# nRF51_key.net
KiCad netlist of a schematic drawn in EAGLE
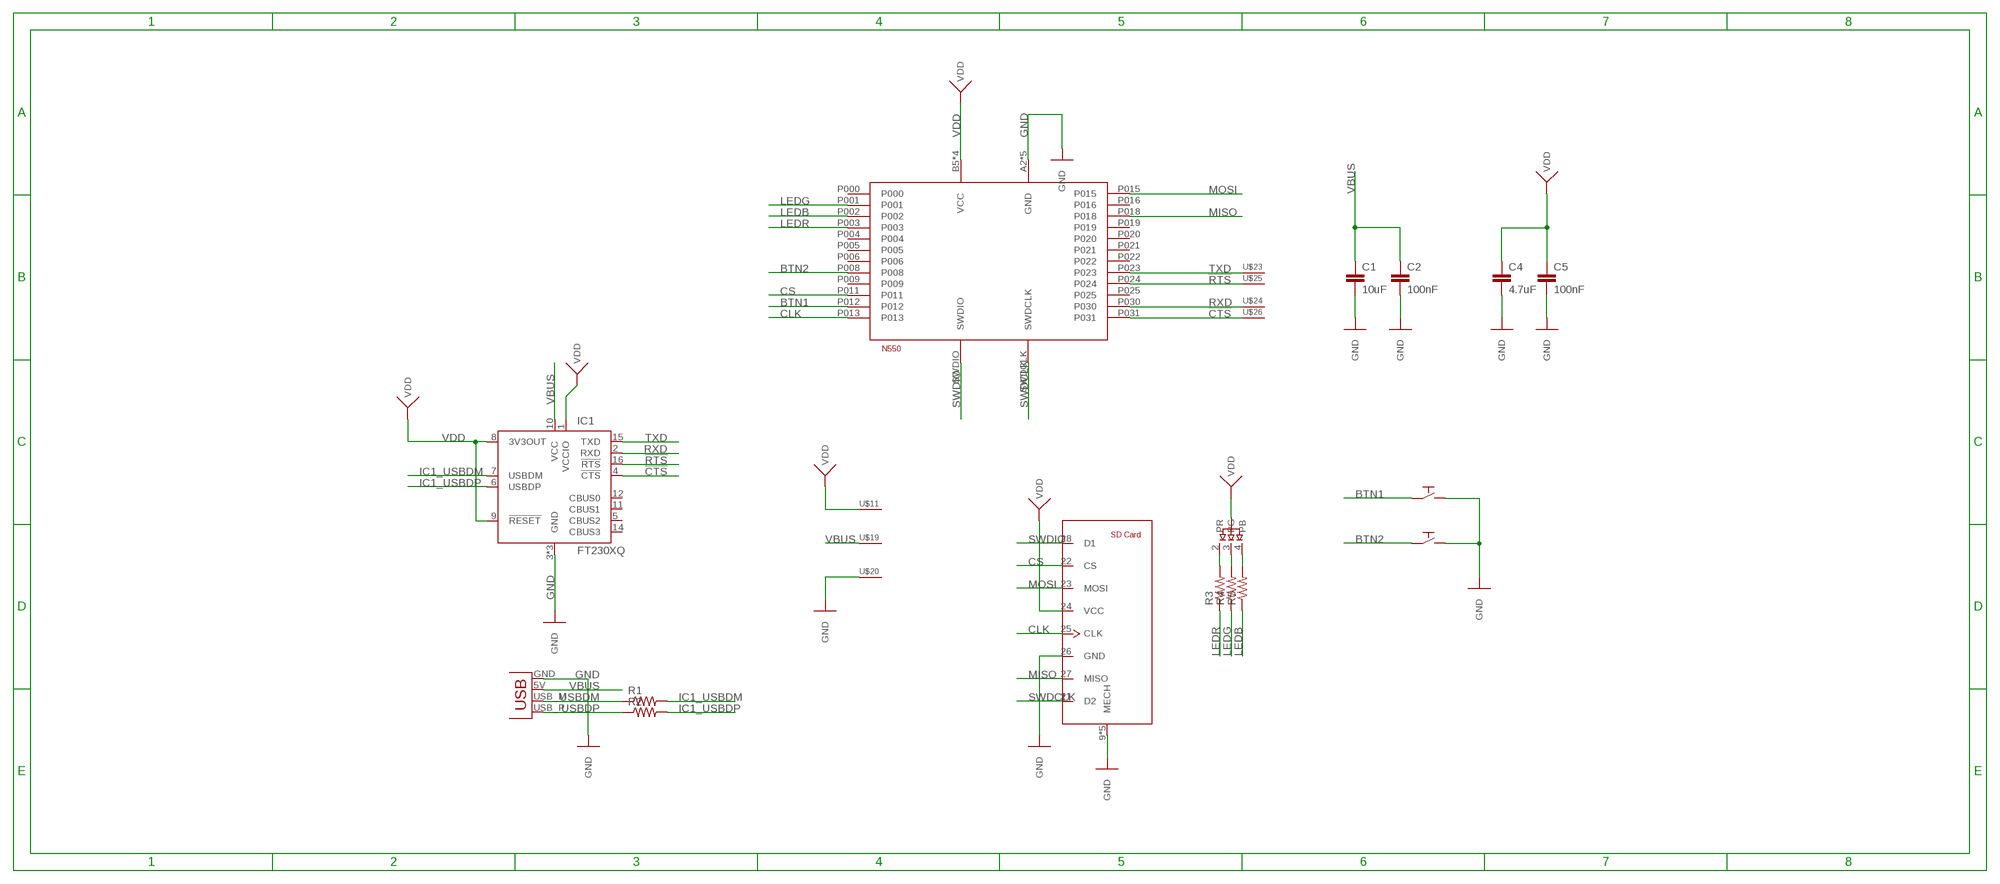
[diagram p0: schematic, sheet 1]

(export (version "E")
  (design (tool "Eeschema 10.0.6"))
  (components
    (comp (ref "C1")
      (value "10uF")
      (footprint "eagle-import:C0603")
      (libsource (lib "eagle-import") (part "CAPACITOR0603"))
    )
    (comp (ref "C2")
      (value "100nF")
      (footprint "eagle-import:C0603")
      (libsource (lib "eagle-import") (part "CAPACITOR0603"))
    )
    (comp (ref "C4")
      (value "4.7uF")
      (footprint "eagle-import:C0603")
      (libsource (lib "eagle-import") (part "CAPACITOR0603"))
    )
    (comp (ref "C5")
      (value "100nF")
      (footprint "eagle-import:C0603")
      (libsource (lib "eagle-import") (part "CAPACITOR0603"))
    )
    (comp (ref "D1")
      (value "LRTBR48G")
      (footprint "eagle-import:LRTBR48GP9Q71R7S526NP68")
      (libsource (lib "eagle-import") (part "LRTBR48G"))
    )
    (comp (ref "IC1")
      (value "FT230XQ")
      (footprint "eagle-import:QFN16")
      (fields (field (name "MF") "FTDI"))
      (libsource (lib "eagle-import") (part "FT230XQ"))
    )
    (comp (ref "J1")
      (value "47571-0001")
      (footprint "eagle-import:47571-0001")
      (libsource (lib "eagle-import") (part "47571-0001"))
    )
    (comp (ref "R1")
      (value "RESISTOR0603")
      (footprint "eagle-import:R0603")
      (libsource (lib "eagle-import") (part "RESISTOR0603"))
    )
    (comp (ref "R2")
      (value "RESISTOR0603")
      (footprint "eagle-import:R0603")
      (libsource (lib "eagle-import") (part "RESISTOR0603"))
    )
    (comp (ref "R3")
      (value "RESISTOR0603")
      (footprint "eagle-import:R0603")
      (libsource (lib "eagle-import") (part "RESISTOR0603"))
    )
    (comp (ref "R4")
      (value "RESISTOR0603")
      (footprint "eagle-import:R0603")
      (libsource (lib "eagle-import") (part "RESISTOR0603"))
    )
    (comp (ref "R5")
      (value "RESISTOR0603")
      (footprint "eagle-import:R0603")
      (libsource (lib "eagle-import") (part "RESISTOR0603"))
    )
    (comp (ref "SPST1")
      (value "PTS526SK08")
      (footprint "eagle-import:PTS526SKG15SMTR2LFS")
      (libsource (lib "eagle-import") (part "PTS526SK08"))
    )
    (comp (ref "SPST2")
      (value "PTS526SK08")
      (footprint "eagle-import:PTS526SKG15SMTR2LFS")
      (libsource (lib "eagle-import") (part "PTS526SK08"))
    )
    (comp (ref "U$1")
      (value "N550")
      (footprint "eagle-import:N550")
      (libsource (lib "eagle-import") (part "N550"))
    )
    (comp (ref "U$11")
      (value "PAD")
      (footprint "eagle-import:PAD_0.8")
      (libsource (lib "eagle-import") (part "PAD"))
    )
    (comp (ref "U$19")
      (value "PAD")
      (footprint "eagle-import:PAD_0.8")
      (libsource (lib "eagle-import") (part "PAD"))
    )
    (comp (ref "U$20")
      (value "PAD")
      (footprint "eagle-import:PAD_0.8")
      (libsource (lib "eagle-import") (part "PAD"))
    )
    (comp (ref "U$23")
      (value "PAD")
      (footprint "eagle-import:PAD_0.8")
      (libsource (lib "eagle-import") (part "PAD"))
    )
    (comp (ref "U$24")
      (value "PAD")
      (footprint "eagle-import:PAD_0.8")
      (libsource (lib "eagle-import") (part "PAD"))
    )
    (comp (ref "U$25")
      (value "PAD")
      (footprint "eagle-import:PAD_0.8")
      (libsource (lib "eagle-import") (part "PAD"))
    )
    (comp (ref "U$26")
      (value "PAD")
      (footprint "eagle-import:PAD_0.8")
      (libsource (lib "eagle-import") (part "PAD"))
    )
    (comp (ref "X1")
      (value "USBPCB")
      (footprint "eagle-import:USB-A-PCB")
      (libsource (lib "eagle-import") (part "USBPCB"))
    )
  )
  (nets
    (net (code "1") (name "/BTN1") (class "Default")
      (node (ref "SPST1") (pin "1") (pinfunction "P$1_1") (pintype "passive"))
      (node (ref "SPST1") (pin "2") (pinfunction "P$1_2") (pintype "passive"))
      (node (ref "U$1") (pin "P012") (pinfunction "P012_P012") (pintype "bidirectional"))
    )
    (net (code "2") (name "/BTN2") (class "Default")
      (node (ref "SPST2") (pin "1") (pinfunction "P$1_1") (pintype "passive"))
      (node (ref "SPST2") (pin "2") (pinfunction "P$1_2") (pintype "passive"))
      (node (ref "U$1") (pin "P008") (pinfunction "P008_P008") (pintype "bidirectional"))
    )
    (net (code "3") (name "/CLK") (class "Default")
      (node (ref "J1") (pin "25") (pinfunction "CLK_25") (pintype "input"))
      (node (ref "U$1") (pin "P013") (pinfunction "P013_P013") (pintype "bidirectional"))
    )
    (net (code "4") (name "/CS") (class "Default")
      (node (ref "J1") (pin "22") (pinfunction "CS_22") (pintype "bidirectional"))
      (node (ref "U$1") (pin "P011") (pinfunction "P011_P011") (pintype "bidirectional"))
    )
    (net (code "5") (name "/IC1_USBDM") (class "Default")
      (node (ref "IC1") (pin "7") (pinfunction "USBDM_7") (pintype "input"))
      (node (ref "R1") (pin "2") (pinfunction "2_2") (pintype "passive"))
    )
    (net (code "6") (name "/IC1_USBDP") (class "Default")
      (node (ref "IC1") (pin "6") (pinfunction "USBDP_6") (pintype "input"))
      (node (ref "R2") (pin "2") (pinfunction "2_2") (pintype "passive"))
    )
    (net (code "7") (name "/LEDB") (class "Default")
      (node (ref "R5") (pin "1") (pinfunction "1_1") (pintype "passive"))
      (node (ref "U$1") (pin "P002") (pinfunction "P002_P002") (pintype "bidirectional"))
    )
    (net (code "8") (name "/LEDG") (class "Default")
      (node (ref "R4") (pin "1") (pinfunction "1_1") (pintype "passive"))
      (node (ref "U$1") (pin "P001") (pinfunction "P001_P001") (pintype "bidirectional"))
    )
    (net (code "9") (name "/LEDR") (class "Default")
      (node (ref "R3") (pin "1") (pinfunction "1_1") (pintype "passive"))
      (node (ref "U$1") (pin "P003") (pinfunction "P003_P003") (pintype "bidirectional"))
    )
    (net (code "10") (name "/MISO") (class "Default")
      (node (ref "J1") (pin "27") (pinfunction "MISO_27") (pintype "bidirectional"))
      (node (ref "U$1") (pin "P018") (pinfunction "P018_P018") (pintype "bidirectional"))
    )
    (net (code "11") (name "/MOSI") (class "Default")
      (node (ref "J1") (pin "23") (pinfunction "MOSI_23") (pintype "bidirectional"))
      (node (ref "U$1") (pin "P015") (pinfunction "P015_P015") (pintype "bidirectional"))
    )
    (net (code "12") (name "/RXD") (class "Default")
      (node (ref "IC1") (pin "2") (pinfunction "RXD_2") (pintype "input"))
      (node (ref "U$1") (pin "P030") (pinfunction "P030_P030") (pintype "bidirectional"))
      (node (ref "U$24") (pin "PAD") (pinfunction "P$1_PAD") (pintype "bidirectional"))
    )
    (net (code "13") (name "/SWDCLK") (class "Default")
      (node (ref "J1") (pin "21") (pinfunction "D2_21") (pintype "tri_state"))
      (node (ref "U$1") (pin "SWDCLK") (pinfunction "SWDCLK_SWDCLK") (pintype "bidirectional"))
    )
    (net (code "14") (name "/SWDIO") (class "Default")
      (node (ref "J1") (pin "28") (pinfunction "D1_28") (pintype "tri_state"))
      (node (ref "U$1") (pin "SWDIO") (pinfunction "SWDIO_SWDIO") (pintype "bidirectional"))
    )
    (net (code "15") (name "/TXD") (class "Default")
      (node (ref "IC1") (pin "15") (pinfunction "TXD_15") (pintype "output"))
      (node (ref "U$1") (pin "P023") (pinfunction "P023_P023") (pintype "bidirectional"))
      (node (ref "U$23") (pin "PAD") (pinfunction "P$1_PAD") (pintype "bidirectional"))
    )
    (net (code "16") (name "/USBDM") (class "Default")
      (node (ref "R1") (pin "1") (pinfunction "1_1") (pintype "passive"))
      (node (ref "X1") (pin "USB_M") (pinfunction "D-_USB_M") (pintype "bidirectional"))
    )
    (net (code "17") (name "/USBDP") (class "Default")
      (node (ref "R2") (pin "1") (pinfunction "1_1") (pintype "passive"))
      (node (ref "X1") (pin "USB_P") (pinfunction "D+_USB_P") (pintype "bidirectional"))
    )
    (net (code "18") (name "/VBUS") (class "Default")
      (node (ref "C1") (pin "1") (pinfunction "1_1") (pintype "passive"))
      (node (ref "C2") (pin "1") (pinfunction "1_1") (pintype "passive"))
      (node (ref "IC1") (pin "10") (pinfunction "VCC_10") (pintype "power_in"))
      (node (ref "U$19") (pin "PAD") (pinfunction "P$1_PAD") (pintype "bidirectional"))
      (node (ref "X1") (pin "5V") (pinfunction "VBUS_5V") (pintype "bidirectional"))
    )
    (net (code "19") (name "/~{CTS}") (class "Default")
      (node (ref "IC1") (pin "4") (pinfunction "~{CTS}_4") (pintype "input"))
      (node (ref "U$1") (pin "P031") (pinfunction "P031_P031") (pintype "bidirectional"))
      (node (ref "U$26") (pin "PAD") (pinfunction "P$1_PAD") (pintype "bidirectional"))
    )
    (net (code "20") (name "/~{RTS}") (class "Default")
      (node (ref "IC1") (pin "16") (pinfunction "~{RTS}_16") (pintype "output"))
      (node (ref "U$1") (pin "P024") (pinfunction "P024_P024") (pintype "bidirectional"))
      (node (ref "U$25") (pin "PAD") (pinfunction "P$1_PAD") (pintype "bidirectional"))
    )
    (net (code "21") (name "GND") (class "Default")
      (node (ref "C1") (pin "2") (pinfunction "2_2") (pintype "passive"))
      (node (ref "C2") (pin "2") (pinfunction "2_2") (pintype "passive"))
      (node (ref "C4") (pin "2") (pinfunction "2_2") (pintype "passive"))
      (node (ref "C5") (pin "2") (pinfunction "2_2") (pintype "passive"))
      (node (ref "IC1") (pin "13") (pinfunction "GND_13") (pintype "power_in"))
      (node (ref "IC1") (pin "3") (pinfunction "GND_3") (pintype "power_in"))
      (node (ref "IC1") (pin "EXP") (pinfunction "GND_EXP") (pintype "power_in"))
      (node (ref "J1") (pin "10") (pinfunction "MECH_10") (pintype "bidirectional"))
      (node (ref "J1") (pin "11") (pinfunction "MECH_11") (pintype "bidirectional"))
      (node (ref "J1") (pin "12") (pinfunction "MECH_12") (pintype "bidirectional"))
      (node (ref "J1") (pin "13") (pinfunction "MECH_13") (pintype "bidirectional"))
      (node (ref "J1") (pin "26") (pinfunction "GND_26") (pintype "power_in"))
      (node (ref "J1") (pin "9") (pinfunction "MECH_9") (pintype "bidirectional"))
      (node (ref "SPST1") (pin "3") (pinfunction "P$2_3") (pintype "passive"))
      (node (ref "SPST1") (pin "4") (pinfunction "P$2_4") (pintype "passive"))
      (node (ref "SPST2") (pin "3") (pinfunction "P$2_3") (pintype "passive"))
      (node (ref "SPST2") (pin "4") (pinfunction "P$2_4") (pintype "passive"))
      (node (ref "U$1") (pin "A2") (pinfunction "GND_A2") (pintype "bidirectional"))
      (node (ref "U$1") (pin "A3") (pinfunction "GND_A3") (pintype "bidirectional"))
      (node (ref "U$1") (pin "A4") (pinfunction "GND_A4") (pintype "bidirectional"))
      (node (ref "U$1") (pin "A5") (pinfunction "GND_A5") (pintype "bidirectional"))
      (node (ref "U$1") (pin "A6") (pinfunction "GND_A6") (pintype "bidirectional"))
      (node (ref "U$20") (pin "PAD") (pinfunction "P$1_PAD") (pintype "bidirectional"))
      (node (ref "X1") (pin "GND") (pinfunction "GND_GND") (pintype "bidirectional"))
    )
    (net (code "22") (name "Net-(D1-PB)") (class "Default")
      (node (ref "D1") (pin "4") (pinfunction "PB_4") (pintype "bidirectional"))
      (node (ref "R5") (pin "2") (pinfunction "2_2") (pintype "passive"))
    )
    (net (code "23") (name "Net-(D1-PG)") (class "Default")
      (node (ref "D1") (pin "3") (pinfunction "PG_3") (pintype "bidirectional"))
      (node (ref "R4") (pin "2") (pinfunction "2_2") (pintype "passive"))
    )
    (net (code "24") (name "Net-(D1-PR)") (class "Default")
      (node (ref "D1") (pin "2") (pinfunction "PR_2") (pintype "bidirectional"))
      (node (ref "R3") (pin "2") (pinfunction "2_2") (pintype "passive"))
    )
    (net (code "25") (name "VDD") (class "Default")
      (node (ref "C4") (pin "1") (pinfunction "1_1") (pintype "passive"))
      (node (ref "C5") (pin "1") (pinfunction "1_1") (pintype "passive"))
      (node (ref "D1") (pin "1") (pinfunction "P$1_1") (pintype "bidirectional"))
      (node (ref "IC1") (pin "1") (pinfunction "VCCIO_1") (pintype "power_in"))
      (node (ref "IC1") (pin "8") (pinfunction "3V3OUT_8") (pintype "passive"))
      (node (ref "IC1") (pin "9") (pinfunction "~{RESET}_9") (pintype "input"))
      (node (ref "J1") (pin "24") (pinfunction "VCC_24") (pintype "power_in"))
      (node (ref "U$1") (pin "B5") (pinfunction "VCC_B5") (pintype "bidirectional"))
      (node (ref "U$1") (pin "B6") (pinfunction "VCC_B6") (pintype "bidirectional"))
      (node (ref "U$1") (pin "C5") (pinfunction "VCC_C5") (pintype "bidirectional"))
      (node (ref "U$1") (pin "C6") (pinfunction "VCC_C6") (pintype "bidirectional"))
      (node (ref "U$11") (pin "PAD") (pinfunction "P$1_PAD") (pintype "bidirectional"))
    )
    (net (code "26") (name "unconnected-(IC1-CBUS0-Pad12)") (class "Default")
      (node (ref "IC1") (pin "12") (pinfunction "CBUS0_12") (pintype "bidirectional"))
    )
    (net (code "27") (name "unconnected-(IC1-CBUS1-Pad11)") (class "Default")
      (node (ref "IC1") (pin "11") (pinfunction "CBUS1_11") (pintype "bidirectional"))
    )
    (net (code "28") (name "unconnected-(IC1-CBUS2-Pad5)") (class "Default")
      (node (ref "IC1") (pin "5") (pinfunction "CBUS2_5") (pintype "bidirectional"))
    )
    (net (code "29") (name "unconnected-(IC1-CBUS3-Pad14)") (class "Default")
      (node (ref "IC1") (pin "14") (pinfunction "CBUS3_14") (pintype "bidirectional"))
    )
    (net (code "30") (name "unconnected-(U$1-PadP000)") (class "Default")
      (node (ref "U$1") (pin "P000") (pinfunction "P000_P000") (pintype "bidirectional"))
    )
    (net (code "31") (name "unconnected-(U$1-PadP004)") (class "Default")
      (node (ref "U$1") (pin "P004") (pinfunction "P004_P004") (pintype "bidirectional"))
    )
    (net (code "32") (name "unconnected-(U$1-PadP005)") (class "Default")
      (node (ref "U$1") (pin "P005") (pinfunction "P005_P005") (pintype "bidirectional"))
    )
    (net (code "33") (name "unconnected-(U$1-PadP006)") (class "Default")
      (node (ref "U$1") (pin "P006") (pinfunction "P006_P006") (pintype "bidirectional"))
    )
    (net (code "34") (name "unconnected-(U$1-PadP009)") (class "Default")
      (node (ref "U$1") (pin "P009") (pinfunction "P009_P009") (pintype "bidirectional"))
    )
    (net (code "35") (name "unconnected-(U$1-PadP016)") (class "Default")
      (node (ref "U$1") (pin "P016") (pinfunction "P016_P016") (pintype "bidirectional"))
    )
    (net (code "36") (name "unconnected-(U$1-PadP019)") (class "Default")
      (node (ref "U$1") (pin "P019") (pinfunction "P019_P019") (pintype "bidirectional"))
    )
    (net (code "37") (name "unconnected-(U$1-PadP020)") (class "Default")
      (node (ref "U$1") (pin "P020") (pinfunction "P020_P020") (pintype "bidirectional"))
    )
    (net (code "38") (name "unconnected-(U$1-PadP021)") (class "Default")
      (node (ref "U$1") (pin "P021") (pinfunction "P021_P021") (pintype "bidirectional"))
    )
    (net (code "39") (name "unconnected-(U$1-PadP022)") (class "Default")
      (node (ref "U$1") (pin "P022") (pinfunction "P022_P022") (pintype "bidirectional"))
    )
    (net (code "40") (name "unconnected-(U$1-PadP025)") (class "Default")
      (node (ref "U$1") (pin "P025") (pinfunction "P025_P025") (pintype "bidirectional"))
    )
  )
)
